# board2.net
KiCad netlist of a schematic drawn in EAGLE
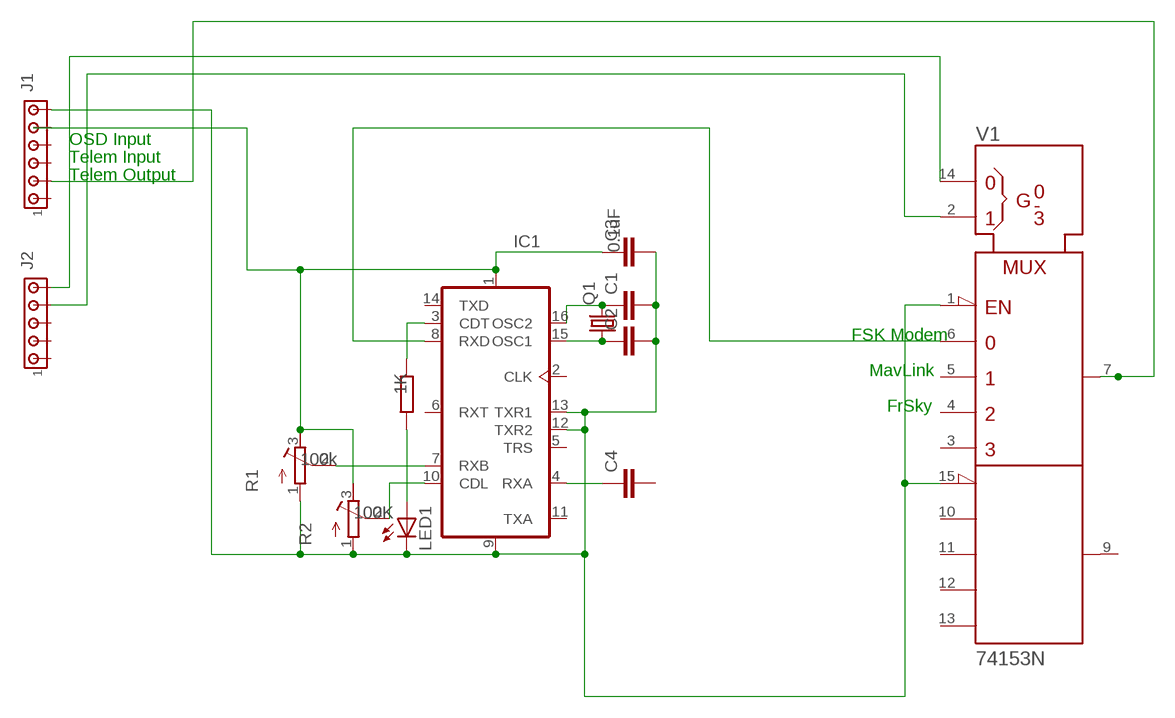
[diagram p0: schematic, sheet 1]

(export (version "E")
  (design (tool "Eeschema 10.0.6"))
  (components
    (comp (ref "C1")
      (value "C2,5-3")
      (footprint "eagle-import:C2.5-3")
      (libsource (lib "eagle-import") (part "C2,5-3"))
    )
    (comp (ref "C2")
      (value "C2,5-3")
      (footprint "eagle-import:C2.5-3")
      (libsource (lib "eagle-import") (part "C2,5-3"))
    )
    (comp (ref "C3")
      (value "C2,5-3")
      (footprint "eagle-import:C2.5-3")
      (fields (field (name "VAL") "0.1uF"))
      (libsource (lib "eagle-import") (part "C2,5-3"))
    )
    (comp (ref "C4")
      (value "C2,5-3")
      (footprint "eagle-import:C2.5-3")
      (libsource (lib "eagle-import") (part "C2,5-3"))
    )
    (comp (ref "IC1")
      (value "TCM3105")
      (footprint "eagle-import:DIL16")
      (libsource (lib "eagle-import") (part "TCM3105"))
    )
    (comp (ref "J1")
      (value "MTA06-100")
      (footprint "eagle-import:10X06MTA")
      (libsource (lib "eagle-import") (part "MTA06-100"))
    )
    (comp (ref "J2")
      (value "MTA05-156")
      (footprint "eagle-import:1X5MTA")
      (libsource (lib "eagle-import") (part "MTA05-156"))
    )
    (comp (ref "LED1")
      (value "LED5MM")
      (footprint "eagle-import:LED5MM")
      (libsource (lib "eagle-import") (part "LED5MM"))
    )
    (comp (ref "Q1")
      (value "CRYSTALHC33U-V")
      (footprint "eagle-import:HC33U-V")
      (libsource (lib "eagle-import") (part "CRYSTALHC33U-V"))
    )
    (comp (ref "R1")
      (value "R-TRIMM64W")
      (footprint "eagle-import:RTRIM64W")
      (fields (field (name "VAL") "100k"))
      (libsource (lib "eagle-import") (part "R-TRIMM64W"))
    )
    (comp (ref "R2")
      (value "R-TRIMM64W")
      (footprint "eagle-import:RTRIM64W")
      (fields (field (name "VAL") "100K"))
      (libsource (lib "eagle-import") (part "R-TRIMM64W"))
    )
    (comp (ref "V1")
      (value "74153N")
      (footprint "eagle-import:DIL16")
      (libsource (lib "eagle-import") (part "74153N"))
    )
  )
  (nets
    (net (code "1") (name "Net-(IC1-CDL)") (class "Default")
      (node (ref "IC1") (pin "10") (pinfunction "CDL_10") (pintype "bidirectional"))
      (node (ref "R2") (pin "2") (pinfunction "S_2") (pintype "passive"))
    )
    (net (code "2") (name "Net-(IC1-OSC1)") (class "Default")
      (node (ref "C2") (pin "1") (pinfunction "1_1") (pintype "passive"))
      (node (ref "IC1") (pin "15") (pinfunction "OSC1_15") (pintype "bidirectional"))
      (node (ref "Q1") (pin "1") (pinfunction "1_1") (pintype "passive"))
    )
    (net (code "3") (name "Net-(IC1-OSC2)") (class "Default")
      (node (ref "C1") (pin "1") (pinfunction "1_1") (pintype "passive"))
      (node (ref "IC1") (pin "16") (pinfunction "OSC2_16") (pintype "bidirectional"))
      (node (ref "Q1") (pin "2") (pinfunction "2_2") (pintype "passive"))
    )
    (net (code "4") (name "Net-(IC1-RXA)") (class "Default")
      (node (ref "C4") (pin "1") (pinfunction "1_1") (pintype "passive"))
      (node (ref "IC1") (pin "4") (pinfunction "RXA_4") (pintype "input"))
    )
    (net (code "5") (name "Net-(IC1-RXB)") (class "Default")
      (node (ref "IC1") (pin "7") (pinfunction "RXB_7") (pintype "bidirectional"))
      (node (ref "R1") (pin "2") (pinfunction "S_2") (pintype "passive"))
    )
    (net (code "6") (name "Net-(IC1-RXD)") (class "Default")
      (node (ref "IC1") (pin "8") (pinfunction "RXD_8") (pintype "output"))
      (node (ref "V1") (pin "6") (pinfunction "1C0_6") (pintype "input"))
    )
    (net (code "7") (name "Net-(IC1-TXR1)") (class "Default")
      (node (ref "C1") (pin "2") (pinfunction "2_2") (pintype "passive"))
      (node (ref "C2") (pin "2") (pinfunction "2_2") (pintype "passive"))
      (node (ref "C3") (pin "2") (pinfunction "2_2") (pintype "passive"))
      (node (ref "IC1") (pin "12") (pinfunction "TXR2_12") (pintype "input"))
      (node (ref "IC1") (pin "13") (pinfunction "TXR1_13") (pintype "input"))
      (node (ref "IC1") (pin "9") (pinfunction "VSS_9") (pintype "power_in"))
      (node (ref "J1") (pin "6") (pinfunction "6_6") (pintype "passive"))
      (node (ref "LED1") (pin "K") (pinfunction "C_K") (pintype "passive"))
      (node (ref "R1") (pin "1") (pinfunction "A_1") (pintype "passive"))
      (node (ref "R2") (pin "1") (pinfunction "A_1") (pintype "passive"))
      (node (ref "V1") (pin "1") (pinfunction "~{1G}_1") (pintype "input"))
      (node (ref "V1") (pin "15") (pinfunction "~{2G}_15") (pintype "input"))
    )
    (net (code "8") (name "Net-(IC1-VDD)") (class "Default")
      (node (ref "C3") (pin "1") (pinfunction "1_1") (pintype "passive"))
      (node (ref "IC1") (pin "1") (pinfunction "VDD_1") (pintype "power_in"))
      (node (ref "J1") (pin "5") (pinfunction "5_5") (pintype "passive"))
      (node (ref "R1") (pin "3") (pinfunction "E_3") (pintype "passive"))
      (node (ref "R2") (pin "3") (pinfunction "E_3") (pintype "passive"))
    )
    (net (code "9") (name "Net-(V1C-1Y)") (class "Default")
      (node (ref "J1") (pin "2") (pinfunction "2_2") (pintype "passive"))
      (node (ref "V1") (pin "7") (pinfunction "1Y_7") (pintype "output"))
    )
    (net (code "10") (name "Net-(V1C-A)") (class "Default")
      (node (ref "J2") (pin "5") (pinfunction "5_5") (pintype "passive"))
      (node (ref "V1") (pin "14") (pinfunction "A_14") (pintype "input"))
    )
    (net (code "11") (name "Net-(V1C-B)") (class "Default")
      (node (ref "J2") (pin "4") (pinfunction "4_4") (pintype "passive"))
      (node (ref "V1") (pin "2") (pinfunction "B_2") (pintype "input"))
    )
    (net (code "12") (name "unconnected-(C4-Pad2)") (class "Default")
      (node (ref "C4") (pin "2") (pinfunction "2_2") (pintype "passive"))
    )
    (net (code "13") (name "unconnected-(IC1-CDT-Pad3)") (class "Default")
      (node (ref "IC1") (pin "3") (pinfunction "CDT_3") (pintype "output"))
    )
    (net (code "14") (name "unconnected-(IC1-CLK-Pad2)") (class "Default")
      (node (ref "IC1") (pin "2") (pinfunction "CLK_2") (pintype "output"))
    )
    (net (code "15") (name "unconnected-(IC1-RXT-Pad6)") (class "Default")
      (node (ref "IC1") (pin "6") (pinfunction "RXT_6") (pintype "bidirectional"))
    )
    (net (code "16") (name "unconnected-(IC1-TRS-Pad5)") (class "Default")
      (node (ref "IC1") (pin "5") (pinfunction "TRS_5") (pintype "input"))
    )
    (net (code "17") (name "unconnected-(IC1-TXA-Pad11)") (class "Default")
      (node (ref "IC1") (pin "11") (pinfunction "TXA_11") (pintype "output"))
    )
    (net (code "18") (name "unconnected-(IC1-TXD-Pad14)") (class "Default")
      (node (ref "IC1") (pin "14") (pinfunction "TXD_14") (pintype "input"))
    )
    (net (code "19") (name "unconnected-(J1-Pad1)") (class "Default")
      (node (ref "J1") (pin "1") (pinfunction "1_1") (pintype "passive"))
    )
    (net (code "20") (name "unconnected-(J1-Pad3)") (class "Default")
      (node (ref "J1") (pin "3") (pinfunction "3_3") (pintype "passive"))
    )
    (net (code "21") (name "unconnected-(J1-Pad4)") (class "Default")
      (node (ref "J1") (pin "4") (pinfunction "4_4") (pintype "passive"))
    )
    (net (code "22") (name "unconnected-(J2-Pad1)") (class "Default")
      (node (ref "J2") (pin "1") (pinfunction "1_1") (pintype "passive"))
    )
    (net (code "23") (name "unconnected-(J2-Pad2)") (class "Default")
      (node (ref "J2") (pin "2") (pinfunction "2_2") (pintype "passive"))
    )
    (net (code "24") (name "unconnected-(J2-Pad3)") (class "Default")
      (node (ref "J2") (pin "3") (pinfunction "3_3") (pintype "passive"))
    )
    (net (code "25") (name "unconnected-(LED1-PadA)") (class "Default")
      (node (ref "LED1") (pin "A") (pinfunction "A_A") (pintype "passive"))
    )
    (net (code "26") (name "unconnected-(V1C-1C1-Pad5)") (class "Default")
      (node (ref "V1") (pin "5") (pinfunction "1C1_5") (pintype "input"))
    )
    (net (code "27") (name "unconnected-(V1C-1C2-Pad4)") (class "Default")
      (node (ref "V1") (pin "4") (pinfunction "1C2_4") (pintype "input"))
    )
    (net (code "28") (name "unconnected-(V1C-1C3-Pad3)") (class "Default")
      (node (ref "V1") (pin "3") (pinfunction "1C3_3") (pintype "input"))
    )
    (net (code "29") (name "unconnected-(V1C-2C0-Pad10)") (class "Default")
      (node (ref "V1") (pin "10") (pinfunction "2C0_10") (pintype "input"))
    )
    (net (code "30") (name "unconnected-(V1C-2C1-Pad11)") (class "Default")
      (node (ref "V1") (pin "11") (pinfunction "2C1_11") (pintype "input"))
    )
    (net (code "31") (name "unconnected-(V1C-2C2-Pad12)") (class "Default")
      (node (ref "V1") (pin "12") (pinfunction "2C2_12") (pintype "input"))
    )
    (net (code "32") (name "unconnected-(V1C-2C3-Pad13)") (class "Default")
      (node (ref "V1") (pin "13") (pinfunction "2C3_13") (pintype "input"))
    )
    (net (code "33") (name "unconnected-(V1C-2Y-Pad9)") (class "Default")
      (node (ref "V1") (pin "9") (pinfunction "2Y_9") (pintype "output"))
    )
  )
)
